# h-bridge.net
KiCad netlist of a schematic drawn in EAGLE
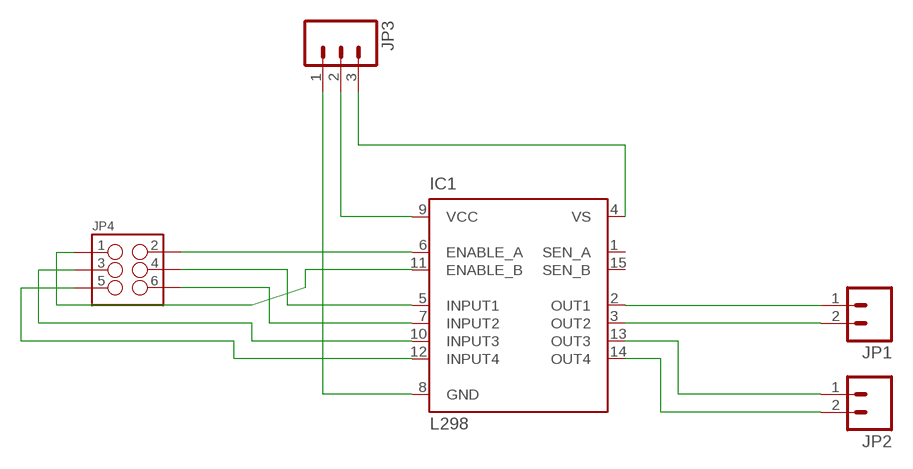
[diagram p0: schematic, sheet 1]

(export (version "E")
  (design (tool "Eeschema 10.0.6"))
  (components
    (comp (ref "IC1")
      (value "L298")
      (footprint "eagle-import:MULTIWATT-15")
      (fields (field (name "MPN") "L298N"))
      (libsource (lib "eagle-import") (part "L298"))
    )
    (comp (ref "JP1")
      (value "M023.5MM")
      (footprint "eagle-import:SCREWTERMINAL-3.5MM-2")
      (libsource (lib "eagle-import") (part "M023.5MM"))
    )
    (comp (ref "JP2")
      (value "M023.5MM")
      (footprint "eagle-import:SCREWTERMINAL-3.5MM-2")
      (libsource (lib "eagle-import") (part "M023.5MM"))
    )
    (comp (ref "JP3")
      (value "M03SCREW")
      (footprint "eagle-import:SCREWTERMINAL-3.5MM-3")
      (libsource (lib "eagle-import") (part "M03SCREW"))
    )
    (comp (ref "JP4")
      (value "M03X22X3_SILK_SM")
      (footprint "eagle-import:2X3")
      (libsource (lib "eagle-import") (part "M03X22X3_SILK_SM"))
    )
  )
  (nets
    (net (code "1") (name "Net-(IC1-ENABLE_A)") (class "Default")
      (node (ref "IC1") (pin "6") (pinfunction "ENABLE_A_6") (pintype "input"))
      (node (ref "JP4") (pin "2") (pinfunction "2_2") (pintype "bidirectional"))
    )
    (net (code "2") (name "Net-(IC1-ENABLE_B)") (class "Default")
      (node (ref "IC1") (pin "11") (pinfunction "ENABLE_B_11") (pintype "input"))
      (node (ref "JP4") (pin "1") (pinfunction "1_1") (pintype "bidirectional"))
    )
    (net (code "3") (name "Net-(IC1-GND)") (class "Default")
      (node (ref "IC1") (pin "8") (pinfunction "GND_8") (pintype "power_in"))
      (node (ref "JP3") (pin "1") (pinfunction "1_1") (pintype "passive"))
    )
    (net (code "4") (name "Net-(IC1-INPUT1)") (class "Default")
      (node (ref "IC1") (pin "5") (pinfunction "INPUT1_5") (pintype "input"))
      (node (ref "JP4") (pin "4") (pinfunction "4_4") (pintype "bidirectional"))
    )
    (net (code "5") (name "Net-(IC1-INPUT2)") (class "Default")
      (node (ref "IC1") (pin "7") (pinfunction "INPUT2_7") (pintype "input"))
      (node (ref "JP4") (pin "6") (pinfunction "6_6") (pintype "bidirectional"))
    )
    (net (code "6") (name "Net-(IC1-INPUT3)") (class "Default")
      (node (ref "IC1") (pin "10") (pinfunction "INPUT3_10") (pintype "input"))
      (node (ref "JP4") (pin "3") (pinfunction "3_3") (pintype "bidirectional"))
    )
    (net (code "7") (name "Net-(IC1-INPUT4)") (class "Default")
      (node (ref "IC1") (pin "12") (pinfunction "INPUT4_12") (pintype "input"))
      (node (ref "JP4") (pin "5") (pinfunction "5_5") (pintype "bidirectional"))
    )
    (net (code "8") (name "Net-(IC1-OUT1)") (class "Default")
      (node (ref "IC1") (pin "2") (pinfunction "OUT1_2") (pintype "output"))
      (node (ref "JP1") (pin "1") (pinfunction "1_1") (pintype "passive"))
    )
    (net (code "9") (name "Net-(IC1-OUT2)") (class "Default")
      (node (ref "IC1") (pin "3") (pinfunction "OUT2_3") (pintype "output"))
      (node (ref "JP1") (pin "2") (pinfunction "2_2") (pintype "passive"))
    )
    (net (code "10") (name "Net-(IC1-OUT3)") (class "Default")
      (node (ref "IC1") (pin "13") (pinfunction "OUT3_13") (pintype "output"))
      (node (ref "JP2") (pin "1") (pinfunction "1_1") (pintype "passive"))
    )
    (net (code "11") (name "Net-(IC1-OUT4)") (class "Default")
      (node (ref "IC1") (pin "14") (pinfunction "OUT4_14") (pintype "output"))
      (node (ref "JP2") (pin "2") (pinfunction "2_2") (pintype "passive"))
    )
    (net (code "12") (name "Net-(IC1-VCC)") (class "Default")
      (node (ref "IC1") (pin "9") (pinfunction "VCC_9") (pintype "power_in"))
      (node (ref "JP3") (pin "2") (pinfunction "2_2") (pintype "passive"))
    )
    (net (code "13") (name "Net-(IC1-VS)") (class "Default")
      (node (ref "IC1") (pin "4") (pinfunction "VS_4") (pintype "power_in"))
      (node (ref "JP3") (pin "3") (pinfunction "3_3") (pintype "passive"))
    )
    (net (code "14") (name "unconnected-(IC1-SEN_A-Pad1)") (class "Default")
      (node (ref "IC1") (pin "1") (pinfunction "SEN_A_1") (pintype "input"))
    )
    (net (code "15") (name "unconnected-(IC1-SEN_B-Pad15)") (class "Default")
      (node (ref "IC1") (pin "15") (pinfunction "SEN_B_15") (pintype "input"))
    )
  )
)
